# M-LVDS_PHY.net
KiCad netlist of a schematic drawn in Altium Designer
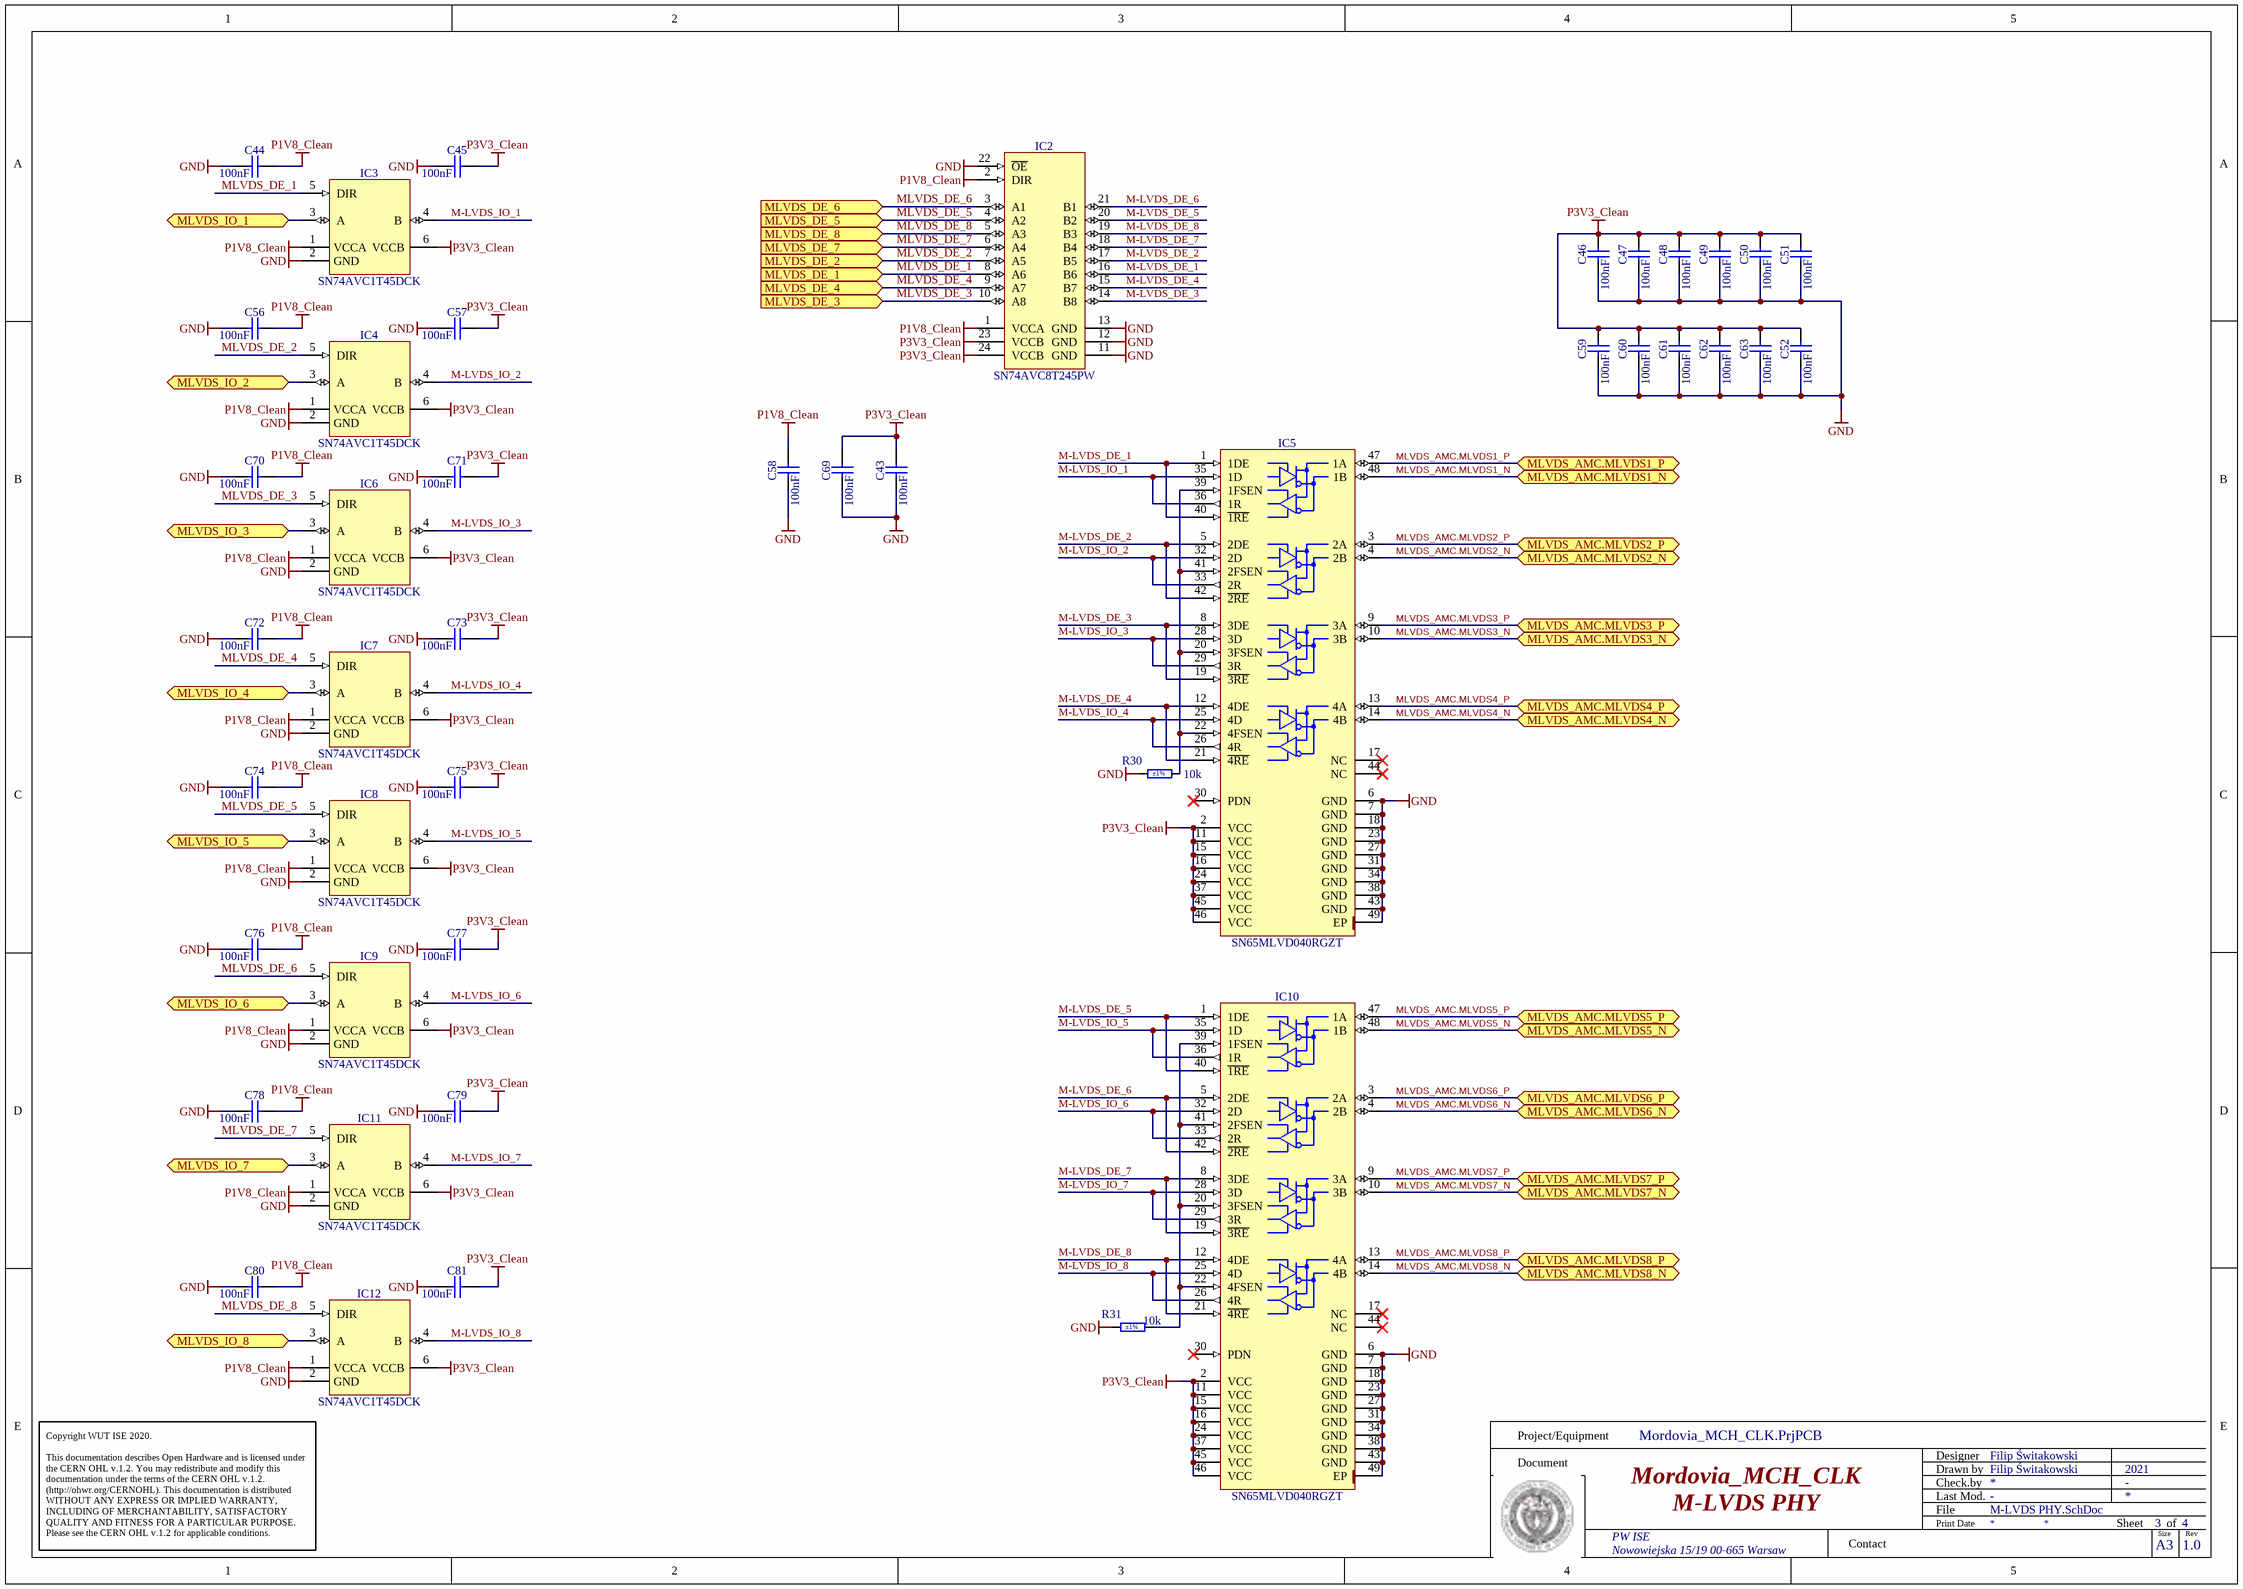
[diagram p0: M-LVDS PHY.SchDoc]

(export (version "E")
  (design (tool "Eeschema 10.0.6"))
  (components
    (comp (ref "C43")
      (value "100nF")
      (footprint "CAPC1005X55N")
      (description "Non-polarised capacitor")
      (fields
        (field (name "PART NUMBER") "CC0402_100NF_50V_10%_X7R")
        (field (name "VOLTAGE") "50V")
        (field (name "AUTHOR") "CERN DEM MR")
      )
      (libsource (lib "Capacitors") (part "Capacitor - non polarized"))
    )
    (comp (ref "C44")
      (value "100nF")
      (footprint "CAPC1005X55N")
      (description "Non-polarised capacitor")
      (fields
        (field (name "PART NUMBER") "CC0402_100NF_50V_10%_X7R")
        (field (name "VOLTAGE") "50V")
        (field (name "AUTHOR") "CERN DEM MR")
      )
      (libsource (lib "Capacitors") (part "Capacitor - non polarized"))
    )
    (comp (ref "C45")
      (value "100nF")
      (footprint "CAPC1005X55N")
      (description "Non-polarised capacitor")
      (fields
        (field (name "PART NUMBER") "CC0402_100NF_50V_10%_X7R")
        (field (name "VOLTAGE") "50V")
        (field (name "AUTHOR") "CERN DEM MR")
      )
      (libsource (lib "Capacitors") (part "Capacitor - non polarized"))
    )
    (comp (ref "C46")
      (value "100nF")
      (footprint "CAPC1005X55N")
      (description "Non-polarised capacitor")
      (fields
        (field (name "PART NUMBER") "CC0402_100NF_50V_10%_X7R")
        (field (name "VOLTAGE") "50V")
        (field (name "AUTHOR") "CERN DEM MR")
      )
      (libsource (lib "Capacitors") (part "Capacitor - non polarized"))
    )
    (comp (ref "C47")
      (value "100nF")
      (footprint "CAPC1005X55N")
      (description "Non-polarised capacitor")
      (fields
        (field (name "PART NUMBER") "CC0402_100NF_50V_10%_X7R")
        (field (name "VOLTAGE") "50V")
        (field (name "AUTHOR") "CERN DEM MR")
      )
      (libsource (lib "Capacitors") (part "Capacitor - non polarized"))
    )
    (comp (ref "C48")
      (value "100nF")
      (footprint "CAPC1005X55N")
      (description "Non-polarised capacitor")
      (fields
        (field (name "PART NUMBER") "CC0402_100NF_50V_10%_X7R")
        (field (name "VOLTAGE") "50V")
        (field (name "AUTHOR") "CERN DEM MR")
      )
      (libsource (lib "Capacitors") (part "Capacitor - non polarized"))
    )
    (comp (ref "C49")
      (value "100nF")
      (footprint "CAPC1005X55N")
      (description "Non-polarised capacitor")
      (fields
        (field (name "PART NUMBER") "CC0402_100NF_50V_10%_X7R")
        (field (name "VOLTAGE") "50V")
        (field (name "AUTHOR") "CERN DEM MR")
      )
      (libsource (lib "Capacitors") (part "Capacitor - non polarized"))
    )
    (comp (ref "C50")
      (value "100nF")
      (footprint "CAPC1005X55N")
      (description "Non-polarised capacitor")
      (fields
        (field (name "PART NUMBER") "CC0402_100NF_50V_10%_X7R")
        (field (name "VOLTAGE") "50V")
        (field (name "AUTHOR") "CERN DEM MR")
      )
      (libsource (lib "Capacitors") (part "Capacitor - non polarized"))
    )
    (comp (ref "C51")
      (value "100nF")
      (footprint "CAPC1005X55N")
      (description "Non-polarised capacitor")
      (fields
        (field (name "PART NUMBER") "CC0402_100NF_50V_10%_X7R")
        (field (name "VOLTAGE") "50V")
        (field (name "AUTHOR") "CERN DEM MR")
      )
      (libsource (lib "Capacitors") (part "Capacitor - non polarized"))
    )
    (comp (ref "C52")
      (value "100nF")
      (footprint "CAPC1005X55N")
      (description "Non-polarised capacitor")
      (fields
        (field (name "PART NUMBER") "CC0402_100NF_50V_10%_X7R")
        (field (name "VOLTAGE") "50V")
        (field (name "AUTHOR") "CERN DEM MR")
      )
      (libsource (lib "Capacitors") (part "Capacitor - non polarized"))
    )
    (comp (ref "C56")
      (value "100nF")
      (footprint "CAPC1005X55N")
      (description "Non-polarised capacitor")
      (fields
        (field (name "PART NUMBER") "CC0402_100NF_50V_10%_X7R")
        (field (name "VOLTAGE") "50V")
        (field (name "AUTHOR") "CERN DEM MR")
      )
      (libsource (lib "Capacitors") (part "Capacitor - non polarized"))
    )
    (comp (ref "C57")
      (value "100nF")
      (footprint "CAPC1005X55N")
      (description "Non-polarised capacitor")
      (fields
        (field (name "PART NUMBER") "CC0402_100NF_50V_10%_X7R")
        (field (name "VOLTAGE") "50V")
        (field (name "AUTHOR") "CERN DEM MR")
      )
      (libsource (lib "Capacitors") (part "Capacitor - non polarized"))
    )
    (comp (ref "C58")
      (value "100nF")
      (footprint "CAPC1005X55N")
      (description "Non-polarised capacitor")
      (fields
        (field (name "PART NUMBER") "CC0402_100NF_50V_10%_X7R")
        (field (name "VOLTAGE") "50V")
        (field (name "AUTHOR") "CERN DEM MR")
      )
      (libsource (lib "Capacitors") (part "Capacitor - non polarized"))
    )
    (comp (ref "C59")
      (value "100nF")
      (footprint "CAPC1005X55N")
      (description "Non-polarised capacitor")
      (fields
        (field (name "PART NUMBER") "CC0402_100NF_50V_10%_X7R")
        (field (name "VOLTAGE") "50V")
        (field (name "AUTHOR") "CERN DEM MR")
      )
      (libsource (lib "Capacitors") (part "Capacitor - non polarized"))
    )
    (comp (ref "C60")
      (value "100nF")
      (footprint "CAPC1005X55N")
      (description "Non-polarised capacitor")
      (fields
        (field (name "PART NUMBER") "CC0402_100NF_50V_10%_X7R")
        (field (name "VOLTAGE") "50V")
        (field (name "AUTHOR") "CERN DEM MR")
      )
      (libsource (lib "Capacitors") (part "Capacitor - non polarized"))
    )
    (comp (ref "C61")
      (value "100nF")
      (footprint "CAPC1005X55N")
      (description "Non-polarised capacitor")
      (fields
        (field (name "PART NUMBER") "CC0402_100NF_50V_10%_X7R")
        (field (name "VOLTAGE") "50V")
        (field (name "AUTHOR") "CERN DEM MR")
      )
      (libsource (lib "Capacitors") (part "Capacitor - non polarized"))
    )
    (comp (ref "C62")
      (value "100nF")
      (footprint "CAPC1005X55N")
      (description "Non-polarised capacitor")
      (fields
        (field (name "PART NUMBER") "CC0402_100NF_50V_10%_X7R")
        (field (name "VOLTAGE") "50V")
        (field (name "AUTHOR") "CERN DEM MR")
      )
      (libsource (lib "Capacitors") (part "Capacitor - non polarized"))
    )
    (comp (ref "C63")
      (value "100nF")
      (footprint "CAPC1005X55N")
      (description "Non-polarised capacitor")
      (fields
        (field (name "PART NUMBER") "CC0402_100NF_50V_10%_X7R")
        (field (name "VOLTAGE") "50V")
        (field (name "AUTHOR") "CERN DEM MR")
      )
      (libsource (lib "Capacitors") (part "Capacitor - non polarized"))
    )
    (comp (ref "C69")
      (value "100nF")
      (footprint "CAPC1005X55N")
      (description "Non-polarised capacitor")
      (fields
        (field (name "PART NUMBER") "CC0402_100NF_50V_10%_X7R")
        (field (name "VOLTAGE") "50V")
        (field (name "AUTHOR") "CERN DEM MR")
      )
      (libsource (lib "Capacitors") (part "Capacitor - non polarized"))
    )
    (comp (ref "C70")
      (value "100nF")
      (footprint "CAPC1005X55N")
      (description "Non-polarised capacitor")
      (fields
        (field (name "PART NUMBER") "CC0402_100NF_50V_10%_X7R")
        (field (name "VOLTAGE") "50V")
        (field (name "AUTHOR") "CERN DEM MR")
      )
      (libsource (lib "Capacitors") (part "Capacitor - non polarized"))
    )
    (comp (ref "C71")
      (value "100nF")
      (footprint "CAPC1005X55N")
      (description "Non-polarised capacitor")
      (fields
        (field (name "PART NUMBER") "CC0402_100NF_50V_10%_X7R")
        (field (name "VOLTAGE") "50V")
        (field (name "AUTHOR") "CERN DEM MR")
      )
      (libsource (lib "Capacitors") (part "Capacitor - non polarized"))
    )
    (comp (ref "C72")
      (value "100nF")
      (footprint "CAPC1005X55N")
      (description "Non-polarised capacitor")
      (fields
        (field (name "PART NUMBER") "CC0402_100NF_50V_10%_X7R")
        (field (name "VOLTAGE") "50V")
        (field (name "AUTHOR") "CERN DEM MR")
      )
      (libsource (lib "Capacitors") (part "Capacitor - non polarized"))
    )
    (comp (ref "C73")
      (value "100nF")
      (footprint "CAPC1005X55N")
      (description "Non-polarised capacitor")
      (fields
        (field (name "PART NUMBER") "CC0402_100NF_50V_10%_X7R")
        (field (name "VOLTAGE") "50V")
        (field (name "AUTHOR") "CERN DEM MR")
      )
      (libsource (lib "Capacitors") (part "Capacitor - non polarized"))
    )
    (comp (ref "C74")
      (value "100nF")
      (footprint "CAPC1005X55N")
      (description "Non-polarised capacitor")
      (fields
        (field (name "PART NUMBER") "CC0402_100NF_50V_10%_X7R")
        (field (name "VOLTAGE") "50V")
        (field (name "AUTHOR") "CERN DEM MR")
      )
      (libsource (lib "Capacitors") (part "Capacitor - non polarized"))
    )
    (comp (ref "C75")
      (value "100nF")
      (footprint "CAPC1005X55N")
      (description "Non-polarised capacitor")
      (fields
        (field (name "PART NUMBER") "CC0402_100NF_50V_10%_X7R")
        (field (name "VOLTAGE") "50V")
        (field (name "AUTHOR") "CERN DEM MR")
      )
      (libsource (lib "Capacitors") (part "Capacitor - non polarized"))
    )
    (comp (ref "C76")
      (value "100nF")
      (footprint "CAPC1005X55N")
      (description "Non-polarised capacitor")
      (fields
        (field (name "PART NUMBER") "CC0402_100NF_50V_10%_X7R")
        (field (name "VOLTAGE") "50V")
        (field (name "AUTHOR") "CERN DEM MR")
      )
      (libsource (lib "Capacitors") (part "Capacitor - non polarized"))
    )
    (comp (ref "C77")
      (value "100nF")
      (footprint "CAPC1005X55N")
      (description "Non-polarised capacitor")
      (fields
        (field (name "PART NUMBER") "CC0402_100NF_50V_10%_X7R")
        (field (name "VOLTAGE") "50V")
        (field (name "AUTHOR") "CERN DEM MR")
      )
      (libsource (lib "Capacitors") (part "Capacitor - non polarized"))
    )
    (comp (ref "C78")
      (value "100nF")
      (footprint "CAPC1005X55N")
      (description "Non-polarised capacitor")
      (fields
        (field (name "PART NUMBER") "CC0402_100NF_50V_10%_X7R")
        (field (name "VOLTAGE") "50V")
        (field (name "AUTHOR") "CERN DEM MR")
      )
      (libsource (lib "Capacitors") (part "Capacitor - non polarized"))
    )
    (comp (ref "C79")
      (value "100nF")
      (footprint "CAPC1005X55N")
      (description "Non-polarised capacitor")
      (fields
        (field (name "PART NUMBER") "CC0402_100NF_50V_10%_X7R")
        (field (name "VOLTAGE") "50V")
        (field (name "AUTHOR") "CERN DEM MR")
      )
      (libsource (lib "Capacitors") (part "Capacitor - non polarized"))
    )
    (comp (ref "C80")
      (value "100nF")
      (footprint "CAPC1005X55N")
      (description "Non-polarised capacitor")
      (fields
        (field (name "PART NUMBER") "CC0402_100NF_50V_10%_X7R")
        (field (name "VOLTAGE") "50V")
        (field (name "AUTHOR") "CERN DEM MR")
      )
      (libsource (lib "Capacitors") (part "Capacitor - non polarized"))
    )
    (comp (ref "C81")
      (value "100nF")
      (footprint "CAPC1005X55N")
      (description "Non-polarised capacitor")
      (fields
        (field (name "PART NUMBER") "CC0402_100NF_50V_10%_X7R")
        (field (name "VOLTAGE") "50V")
        (field (name "AUTHOR") "CERN DEM MR")
      )
      (libsource (lib "Capacitors") (part "Capacitor - non polarized"))
    )
    (comp (ref "IC2")
      (value "SN74AVC8T245PW")
      (footprint "SOP65P640X120-24N")
      (description "8-Bit Dual-Supply Bus Transceiver With Configurable Voltage Translation and 3-State Outputs")
      (fields (field (name "MANUFACTURER") "TEXAS INSTRUMENTS") (field (name "AUTHOR") "CERN DEM JLC"))
      (libsource (lib "ICs And Semiconductors") (part "748T245"))
    )
    (comp (ref "IC3")
      (value "SN74AVC1T45DCK")
      (footprint "SOT65P210X110-6N")
      (description "Single-Bit Dual-Supply Bus Transceiver")
      (fields
        (field (name "PART NUMBER") "SN74AVC1T45DCKR")
        (field (name "MANUFACTURER") "TEXAS INSTRUMENTS")
        (field (name "AUTHOR") "CERN DEM JLC")
      )
      (libsource (lib "ICs And Semiconductors") (part "741T45"))
    )
    (comp (ref "IC4")
      (value "SN74AVC1T45DCK")
      (footprint "SOT65P210X110-6N")
      (description "Single-Bit Dual-Supply Bus Transceiver")
      (fields
        (field (name "PART NUMBER") "SN74AVC1T45DCKR")
        (field (name "MANUFACTURER") "TEXAS INSTRUMENTS")
        (field (name "AUTHOR") "CERN DEM JLC")
      )
      (libsource (lib "ICs And Semiconductors") (part "741T45"))
    )
    (comp (ref "IC5")
      (value "SN65MLVD040RGZT")
      (footprint "QFN50P700X700X100-49N-S420")
      (description "4-Channel Half-Duplex M-LVDS Line Transceiver")
      (fields (field (name "MANUFACTURER") "TEXAS INSTRUMENTS") (field (name "AUTHOR") "CERN DEM JLC"))
      (libsource (lib "ICs And Semiconductors") (part "SN65MLVD040"))
    )
    (comp (ref "IC6")
      (value "SN74AVC1T45DCK")
      (footprint "SOT65P210X110-6N")
      (description "Single-Bit Dual-Supply Bus Transceiver")
      (fields
        (field (name "PART NUMBER") "SN74AVC1T45DCKR")
        (field (name "MANUFACTURER") "TEXAS INSTRUMENTS")
        (field (name "AUTHOR") "CERN DEM JLC")
      )
      (libsource (lib "ICs And Semiconductors") (part "741T45"))
    )
    (comp (ref "IC7")
      (value "SN74AVC1T45DCK")
      (footprint "SOT65P210X110-6N")
      (description "Single-Bit Dual-Supply Bus Transceiver")
      (fields
        (field (name "PART NUMBER") "SN74AVC1T45DCKR")
        (field (name "MANUFACTURER") "TEXAS INSTRUMENTS")
        (field (name "AUTHOR") "CERN DEM JLC")
      )
      (libsource (lib "ICs And Semiconductors") (part "741T45"))
    )
    (comp (ref "IC8")
      (value "SN74AVC1T45DCK")
      (footprint "SOT65P210X110-6N")
      (description "Single-Bit Dual-Supply Bus Transceiver")
      (fields
        (field (name "PART NUMBER") "SN74AVC1T45DCKR")
        (field (name "MANUFACTURER") "TEXAS INSTRUMENTS")
        (field (name "AUTHOR") "CERN DEM JLC")
      )
      (libsource (lib "ICs And Semiconductors") (part "741T45"))
    )
    (comp (ref "IC9")
      (value "SN74AVC1T45DCK")
      (footprint "SOT65P210X110-6N")
      (description "Single-Bit Dual-Supply Bus Transceiver")
      (fields
        (field (name "PART NUMBER") "SN74AVC1T45DCKR")
        (field (name "MANUFACTURER") "TEXAS INSTRUMENTS")
        (field (name "AUTHOR") "CERN DEM JLC")
      )
      (libsource (lib "ICs And Semiconductors") (part "741T45"))
    )
    (comp (ref "IC10")
      (value "SN65MLVD040RGZT")
      (footprint "QFN50P700X700X100-49N-S420")
      (description "4-Channel Half-Duplex M-LVDS Line Transceiver")
      (fields (field (name "MANUFACTURER") "TEXAS INSTRUMENTS") (field (name "AUTHOR") "CERN DEM JLC"))
      (libsource (lib "ICs And Semiconductors") (part "SN65MLVD040"))
    )
    (comp (ref "IC11")
      (value "SN74AVC1T45DCK")
      (footprint "SOT65P210X110-6N")
      (description "Single-Bit Dual-Supply Bus Transceiver")
      (fields
        (field (name "PART NUMBER") "SN74AVC1T45DCKR")
        (field (name "MANUFACTURER") "TEXAS INSTRUMENTS")
        (field (name "AUTHOR") "CERN DEM JLC")
      )
      (libsource (lib "ICs And Semiconductors") (part "741T45"))
    )
    (comp (ref "IC12")
      (value "SN74AVC1T45DCK")
      (footprint "SOT65P210X110-6N")
      (description "Single-Bit Dual-Supply Bus Transceiver")
      (fields
        (field (name "PART NUMBER") "SN74AVC1T45DCKR")
        (field (name "MANUFACTURER") "TEXAS INSTRUMENTS")
        (field (name "AUTHOR") "CERN DEM JLC")
      )
      (libsource (lib "ICs And Semiconductors") (part "741T45"))
    )
    (comp (ref "R30")
      (value "10k")
      (footprint "RESC1005X40N")
      (description "Resistor - 1%")
      (fields
        (field (name "TOLERANCE") "±1%")
        (field (name "PART NUMBER") "R0402_10K_1%_0.0625W_100PPM")
        (field (name "POWER") "0.0625W")
        (field (name "AUTHOR") "CERN DEM JLC")
      )
      (libsource (lib "Resistors") (part "Resistor - 1%"))
    )
    (comp (ref "R31")
      (value "10k")
      (footprint "RESC1005X40N")
      (description "Resistor - 1%")
      (fields
        (field (name "TOLERANCE") "±1%")
        (field (name "PART NUMBER") "R0402_10K_1%_0.0625W_100PPM")
        (field (name "POWER") "0.0625W")
        (field (name "AUTHOR") "CERN DEM JLC")
      )
      (libsource (lib "Resistors") (part "Resistor - 1%"))
    )
  )
  (nets
    (net (code "1") (name "/M-LVDS_DE_1") (class "Default")
      (node (ref "IC2") (pin "16") (pinfunction "B6_16") (pintype "bidirectional"))
      (node (ref "IC5") (pin "1") (pinfunction "1DE_1") (pintype "input"))
      (node (ref "IC5") (pin "40") (pinfunction "~{1RE}_40") (pintype "input"))
    )
    (net (code "2") (name "/M-LVDS_DE_2") (class "Default")
      (node (ref "IC2") (pin "17") (pinfunction "B5_17") (pintype "bidirectional"))
      (node (ref "IC5") (pin "42") (pinfunction "~{2RE}_42") (pintype "input"))
      (node (ref "IC5") (pin "5") (pinfunction "2DE_5") (pintype "input"))
    )
    (net (code "3") (name "/M-LVDS_DE_3") (class "Default")
      (node (ref "IC2") (pin "14") (pinfunction "B8_14") (pintype "bidirectional"))
      (node (ref "IC5") (pin "19") (pinfunction "~{3RE}_19") (pintype "input"))
      (node (ref "IC5") (pin "8") (pinfunction "3DE_8") (pintype "input"))
    )
    (net (code "4") (name "/M-LVDS_DE_4") (class "Default")
      (node (ref "IC2") (pin "15") (pinfunction "B7_15") (pintype "bidirectional"))
      (node (ref "IC5") (pin "12") (pinfunction "4DE_12") (pintype "input"))
      (node (ref "IC5") (pin "21") (pinfunction "~{4RE}_21") (pintype "input"))
    )
    (net (code "5") (name "/M-LVDS_DE_5") (class "Default")
      (node (ref "IC10") (pin "1") (pinfunction "1DE_1") (pintype "input"))
      (node (ref "IC10") (pin "40") (pinfunction "~{1RE}_40") (pintype "input"))
      (node (ref "IC2") (pin "20") (pinfunction "B2_20") (pintype "bidirectional"))
    )
    (net (code "6") (name "/M-LVDS_DE_6") (class "Default")
      (node (ref "IC10") (pin "42") (pinfunction "~{2RE}_42") (pintype "input"))
      (node (ref "IC10") (pin "5") (pinfunction "2DE_5") (pintype "input"))
      (node (ref "IC2") (pin "21") (pinfunction "B1_21") (pintype "bidirectional"))
    )
    (net (code "7") (name "/M-LVDS_DE_7") (class "Default")
      (node (ref "IC10") (pin "19") (pinfunction "~{3RE}_19") (pintype "input"))
      (node (ref "IC10") (pin "8") (pinfunction "3DE_8") (pintype "input"))
      (node (ref "IC2") (pin "18") (pinfunction "B4_18") (pintype "bidirectional"))
    )
    (net (code "8") (name "/M-LVDS_DE_8") (class "Default")
      (node (ref "IC10") (pin "12") (pinfunction "4DE_12") (pintype "input"))
      (node (ref "IC10") (pin "21") (pinfunction "~{4RE}_21") (pintype "input"))
      (node (ref "IC2") (pin "19") (pinfunction "B3_19") (pintype "bidirectional"))
    )
    (net (code "9") (name "/M-LVDS_IO_1") (class "Default")
      (node (ref "IC3") (pin "4") (pinfunction "B_4") (pintype "bidirectional"))
      (node (ref "IC5") (pin "35") (pinfunction "1D_35") (pintype "input"))
      (node (ref "IC5") (pin "36") (pinfunction "1R_36") (pintype "output"))
    )
    (net (code "10") (name "/M-LVDS_IO_2") (class "Default")
      (node (ref "IC4") (pin "4") (pinfunction "B_4") (pintype "bidirectional"))
      (node (ref "IC5") (pin "32") (pinfunction "2D_32") (pintype "input"))
      (node (ref "IC5") (pin "33") (pinfunction "2R_33") (pintype "output"))
    )
    (net (code "11") (name "/M-LVDS_IO_3") (class "Default")
      (node (ref "IC5") (pin "28") (pinfunction "3D_28") (pintype "input"))
      (node (ref "IC5") (pin "29") (pinfunction "3R_29") (pintype "output"))
      (node (ref "IC6") (pin "4") (pinfunction "B_4") (pintype "bidirectional"))
    )
    (net (code "12") (name "/M-LVDS_IO_4") (class "Default")
      (node (ref "IC5") (pin "25") (pinfunction "4D_25") (pintype "input"))
      (node (ref "IC5") (pin "26") (pinfunction "4R_26") (pintype "output"))
      (node (ref "IC7") (pin "4") (pinfunction "B_4") (pintype "bidirectional"))
    )
    (net (code "13") (name "/M-LVDS_IO_5") (class "Default")
      (node (ref "IC10") (pin "35") (pinfunction "1D_35") (pintype "input"))
      (node (ref "IC10") (pin "36") (pinfunction "1R_36") (pintype "output"))
      (node (ref "IC8") (pin "4") (pinfunction "B_4") (pintype "bidirectional"))
    )
    (net (code "14") (name "/M-LVDS_IO_6") (class "Default")
      (node (ref "IC10") (pin "32") (pinfunction "2D_32") (pintype "input"))
      (node (ref "IC10") (pin "33") (pinfunction "2R_33") (pintype "output"))
      (node (ref "IC9") (pin "4") (pinfunction "B_4") (pintype "bidirectional"))
    )
    (net (code "15") (name "/M-LVDS_IO_7") (class "Default")
      (node (ref "IC10") (pin "28") (pinfunction "3D_28") (pintype "input"))
      (node (ref "IC10") (pin "29") (pinfunction "3R_29") (pintype "output"))
      (node (ref "IC11") (pin "4") (pinfunction "B_4") (pintype "bidirectional"))
    )
    (net (code "16") (name "/M-LVDS_IO_8") (class "Default")
      (node (ref "IC10") (pin "25") (pinfunction "4D_25") (pintype "input"))
      (node (ref "IC10") (pin "26") (pinfunction "4R_26") (pintype "output"))
      (node (ref "IC12") (pin "4") (pinfunction "B_4") (pintype "bidirectional"))
    )
    (net (code "17") (name "/MLVDS_AMC.MLVDS1_N") (class "Default")
      (node (ref "IC5") (pin "48") (pinfunction "1B_48") (pintype "bidirectional"))
    )
    (net (code "18") (name "/MLVDS_AMC.MLVDS1_P") (class "Default")
      (node (ref "IC5") (pin "47") (pinfunction "1A_47") (pintype "bidirectional"))
    )
    (net (code "19") (name "/MLVDS_AMC.MLVDS2_N") (class "Default")
      (node (ref "IC5") (pin "4") (pinfunction "2B_4") (pintype "bidirectional"))
    )
    (net (code "20") (name "/MLVDS_AMC.MLVDS2_P") (class "Default")
      (node (ref "IC5") (pin "3") (pinfunction "2A_3") (pintype "bidirectional"))
    )
    (net (code "21") (name "/MLVDS_AMC.MLVDS3_N") (class "Default")
      (node (ref "IC5") (pin "10") (pinfunction "3B_10") (pintype "bidirectional"))
    )
    (net (code "22") (name "/MLVDS_AMC.MLVDS3_P") (class "Default")
      (node (ref "IC5") (pin "9") (pinfunction "3A_9") (pintype "bidirectional"))
    )
    (net (code "23") (name "/MLVDS_AMC.MLVDS4_N") (class "Default")
      (node (ref "IC5") (pin "14") (pinfunction "4B_14") (pintype "bidirectional"))
    )
    (net (code "24") (name "/MLVDS_AMC.MLVDS4_P") (class "Default")
      (node (ref "IC5") (pin "13") (pinfunction "4A_13") (pintype "bidirectional"))
    )
    (net (code "25") (name "/MLVDS_AMC.MLVDS5_N") (class "Default")
      (node (ref "IC10") (pin "48") (pinfunction "1B_48") (pintype "bidirectional"))
    )
    (net (code "26") (name "/MLVDS_AMC.MLVDS5_P") (class "Default")
      (node (ref "IC10") (pin "47") (pinfunction "1A_47") (pintype "bidirectional"))
    )
    (net (code "27") (name "/MLVDS_AMC.MLVDS6_N") (class "Default")
      (node (ref "IC10") (pin "4") (pinfunction "2B_4") (pintype "bidirectional"))
    )
    (net (code "28") (name "/MLVDS_AMC.MLVDS6_P") (class "Default")
      (node (ref "IC10") (pin "3") (pinfunction "2A_3") (pintype "bidirectional"))
    )
    (net (code "29") (name "/MLVDS_AMC.MLVDS7_N") (class "Default")
      (node (ref "IC10") (pin "10") (pinfunction "3B_10") (pintype "bidirectional"))
    )
    (net (code "30") (name "/MLVDS_AMC.MLVDS7_P") (class "Default")
      (node (ref "IC10") (pin "9") (pinfunction "3A_9") (pintype "bidirectional"))
    )
    (net (code "31") (name "/MLVDS_AMC.MLVDS8_N") (class "Default")
      (node (ref "IC10") (pin "14") (pinfunction "4B_14") (pintype "bidirectional"))
    )
    (net (code "32") (name "/MLVDS_AMC.MLVDS8_P") (class "Default")
      (node (ref "IC10") (pin "13") (pinfunction "4A_13") (pintype "bidirectional"))
    )
    (net (code "33") (name "/MLVDS_DE_1") (class "Default")
      (node (ref "IC2") (pin "8") (pinfunction "A6_8") (pintype "bidirectional"))
      (node (ref "IC3") (pin "5") (pinfunction "DIR_5") (pintype "input"))
    )
    (net (code "34") (name "/MLVDS_DE_2") (class "Default")
      (node (ref "IC2") (pin "7") (pinfunction "A5_7") (pintype "bidirectional"))
      (node (ref "IC4") (pin "5") (pinfunction "DIR_5") (pintype "input"))
    )
    (net (code "35") (name "/MLVDS_DE_3") (class "Default")
      (node (ref "IC2") (pin "10") (pinfunction "A8_10") (pintype "bidirectional"))
      (node (ref "IC6") (pin "5") (pinfunction "DIR_5") (pintype "input"))
    )
    (net (code "36") (name "/MLVDS_DE_4") (class "Default")
      (node (ref "IC2") (pin "9") (pinfunction "A7_9") (pintype "bidirectional"))
      (node (ref "IC7") (pin "5") (pinfunction "DIR_5") (pintype "input"))
    )
    (net (code "37") (name "/MLVDS_DE_5") (class "Default")
      (node (ref "IC2") (pin "4") (pinfunction "A2_4") (pintype "bidirectional"))
      (node (ref "IC8") (pin "5") (pinfunction "DIR_5") (pintype "input"))
    )
    (net (code "38") (name "/MLVDS_DE_6") (class "Default")
      (node (ref "IC2") (pin "3") (pinfunction "A1_3") (pintype "bidirectional"))
      (node (ref "IC9") (pin "5") (pinfunction "DIR_5") (pintype "input"))
    )
    (net (code "39") (name "/MLVDS_DE_7") (class "Default")
      (node (ref "IC11") (pin "5") (pinfunction "DIR_5") (pintype "input"))
      (node (ref "IC2") (pin "6") (pinfunction "A4_6") (pintype "bidirectional"))
    )
    (net (code "40") (name "/MLVDS_DE_8") (class "Default")
      (node (ref "IC12") (pin "5") (pinfunction "DIR_5") (pintype "input"))
      (node (ref "IC2") (pin "5") (pinfunction "A3_5") (pintype "bidirectional"))
    )
    (net (code "41") (name "/MLVDS_IO_1") (class "Default")
      (node (ref "IC3") (pin "3") (pinfunction "A_3") (pintype "bidirectional"))
    )
    (net (code "42") (name "/MLVDS_IO_2") (class "Default")
      (node (ref "IC4") (pin "3") (pinfunction "A_3") (pintype "bidirectional"))
    )
    (net (code "43") (name "/MLVDS_IO_3") (class "Default")
      (node (ref "IC6") (pin "3") (pinfunction "A_3") (pintype "bidirectional"))
    )
    (net (code "44") (name "/MLVDS_IO_4") (class "Default")
      (node (ref "IC7") (pin "3") (pinfunction "A_3") (pintype "bidirectional"))
    )
    (net (code "45") (name "/MLVDS_IO_5") (class "Default")
      (node (ref "IC8") (pin "3") (pinfunction "A_3") (pintype "bidirectional"))
    )
    (net (code "46") (name "/MLVDS_IO_6") (class "Default")
      (node (ref "IC9") (pin "3") (pinfunction "A_3") (pintype "bidirectional"))
    )
    (net (code "47") (name "/MLVDS_IO_7") (class "Default")
      (node (ref "IC11") (pin "3") (pinfunction "A_3") (pintype "bidirectional"))
    )
    (net (code "48") (name "/MLVDS_IO_8") (class "Default")
      (node (ref "IC12") (pin "3") (pinfunction "A_3") (pintype "bidirectional"))
    )
    (net (code "49") (name "GND") (class "Default")
      (node (ref "C43") (pin "1") (pinfunction "1_1") (pintype "passive"))
      (node (ref "C44") (pin "1") (pinfunction "1_1") (pintype "passive"))
      (node (ref "C45") (pin "1") (pinfunction "1_1") (pintype "passive"))
      (node (ref "C46") (pin "1") (pinfunction "1_1") (pintype "passive"))
      (node (ref "C47") (pin "1") (pinfunction "1_1") (pintype "passive"))
      (node (ref "C48") (pin "1") (pinfunction "1_1") (pintype "passive"))
      (node (ref "C49") (pin "1") (pinfunction "1_1") (pintype "passive"))
      (node (ref "C50") (pin "1") (pinfunction "1_1") (pintype "passive"))
      (node (ref "C51") (pin "1") (pinfunction "1_1") (pintype "passive"))
      (node (ref "C52") (pin "1") (pinfunction "1_1") (pintype "passive"))
      (node (ref "C56") (pin "1") (pinfunction "1_1") (pintype "passive"))
      (node (ref "C57") (pin "1") (pinfunction "1_1") (pintype "passive"))
      (node (ref "C58") (pin "1") (pinfunction "1_1") (pintype "passive"))
      (node (ref "C59") (pin "1") (pinfunction "1_1") (pintype "passive"))
      (node (ref "C60") (pin "1") (pinfunction "1_1") (pintype "passive"))
      (node (ref "C61") (pin "1") (pinfunction "1_1") (pintype "passive"))
      (node (ref "C62") (pin "1") (pinfunction "1_1") (pintype "passive"))
      (node (ref "C63") (pin "1") (pinfunction "1_1") (pintype "passive"))
      (node (ref "C69") (pin "1") (pinfunction "1_1") (pintype "passive"))
      (node (ref "C70") (pin "1") (pinfunction "1_1") (pintype "passive"))
      (node (ref "C71") (pin "1") (pinfunction "1_1") (pintype "passive"))
      (node (ref "C72") (pin "1") (pinfunction "1_1") (pintype "passive"))
      (node (ref "C73") (pin "1") (pinfunction "1_1") (pintype "passive"))
      (node (ref "C74") (pin "1") (pinfunction "1_1") (pintype "passive"))
      (node (ref "C75") (pin "1") (pinfunction "1_1") (pintype "passive"))
      (node (ref "C76") (pin "1") (pinfunction "1_1") (pintype "passive"))
      (node (ref "C77") (pin "1") (pinfunction "1_1") (pintype "passive"))
      (node (ref "C78") (pin "1") (pinfunction "1_1") (pintype "passive"))
      (node (ref "C79") (pin "1") (pinfunction "1_1") (pintype "passive"))
      (node (ref "C80") (pin "1") (pinfunction "1_1") (pintype "passive"))
      (node (ref "C81") (pin "1") (pinfunction "1_1") (pintype "passive"))
      (node (ref "IC10") (pin "18") (pinfunction "GND_18") (pintype "power_in"))
      (node (ref "IC10") (pin "23") (pinfunction "GND_23") (pintype "power_in"))
      (node (ref "IC10") (pin "27") (pinfunction "GND_27") (pintype "power_in"))
      (node (ref "IC10") (pin "31") (pinfunction "GND_31") (pintype "power_in"))
      (node (ref "IC10") (pin "34") (pinfunction "GND_34") (pintype "power_in"))
      (node (ref "IC10") (pin "38") (pinfunction "GND_38") (pintype "power_in"))
      (node (ref "IC10") (pin "43") (pinfunction "GND_43") (pintype "power_in"))
      (node (ref "IC10") (pin "49") (pinfunction "EP_49") (pintype "power_in"))
      (node (ref "IC10") (pin "6") (pinfunction "GND_6") (pintype "power_in"))
      (node (ref "IC10") (pin "7") (pinfunction "GND_7") (pintype "power_in"))
      (node (ref "IC11") (pin "2") (pinfunction "GND_2") (pintype "power_in"))
      (node (ref "IC12") (pin "2") (pinfunction "GND_2") (pintype "power_in"))
      (node (ref "IC2") (pin "11") (pinfunction "GND_11") (pintype "power_in"))
      (node (ref "IC2") (pin "12") (pinfunction "GND_12") (pintype "power_in"))
      (node (ref "IC2") (pin "13") (pinfunction "GND_13") (pintype "power_in"))
      (node (ref "IC2") (pin "22") (pinfunction "~{OE}_22") (pintype "input"))
      (node (ref "IC3") (pin "2") (pinfunction "GND_2") (pintype "power_in"))
      (node (ref "IC4") (pin "2") (pinfunction "GND_2") (pintype "power_in"))
      (node (ref "IC5") (pin "18") (pinfunction "GND_18") (pintype "power_in"))
      (node (ref "IC5") (pin "23") (pinfunction "GND_23") (pintype "power_in"))
      (node (ref "IC5") (pin "27") (pinfunction "GND_27") (pintype "power_in"))
      (node (ref "IC5") (pin "31") (pinfunction "GND_31") (pintype "power_in"))
      (node (ref "IC5") (pin "34") (pinfunction "GND_34") (pintype "power_in"))
      (node (ref "IC5") (pin "38") (pinfunction "GND_38") (pintype "power_in"))
      (node (ref "IC5") (pin "43") (pinfunction "GND_43") (pintype "power_in"))
      (node (ref "IC5") (pin "49") (pinfunction "EP_49") (pintype "power_in"))
      (node (ref "IC5") (pin "6") (pinfunction "GND_6") (pintype "power_in"))
      (node (ref "IC5") (pin "7") (pinfunction "GND_7") (pintype "power_in"))
      (node (ref "IC6") (pin "2") (pinfunction "GND_2") (pintype "power_in"))
      (node (ref "IC7") (pin "2") (pinfunction "GND_2") (pintype "power_in"))
      (node (ref "IC8") (pin "2") (pinfunction "GND_2") (pintype "power_in"))
      (node (ref "IC9") (pin "2") (pinfunction "GND_2") (pintype "power_in"))
      (node (ref "R30") (pin "1") (pinfunction "1_1") (pintype "passive"))
      (node (ref "R31") (pin "1") (pinfunction "1_1") (pintype "passive"))
    )
    (net (code "50") (name "Net-(IC5-1FSEN)") (class "Default")
      (node (ref "IC5") (pin "20") (pinfunction "3FSEN_20") (pintype "input"))
      (node (ref "IC5") (pin "22") (pinfunction "4FSEN_22") (pintype "input"))
      (node (ref "IC5") (pin "39") (pinfunction "1FSEN_39") (pintype "input"))
      (node (ref "IC5") (pin "41") (pinfunction "2FSEN_41") (pintype "input"))
      (node (ref "R30") (pin "2") (pinfunction "2_2") (pintype "passive"))
    )
    (net (code "51") (name "Net-(IC10-1FSEN)") (class "Default")
      (node (ref "IC10") (pin "20") (pinfunction "3FSEN_20") (pintype "input"))
      (node (ref "IC10") (pin "22") (pinfunction "4FSEN_22") (pintype "input"))
      (node (ref "IC10") (pin "39") (pinfunction "1FSEN_39") (pintype "input"))
      (node (ref "IC10") (pin "41") (pinfunction "2FSEN_41") (pintype "input"))
      (node (ref "R31") (pin "2") (pinfunction "2_2") (pintype "passive"))
    )
    (net (code "52") (name "P1V8_Clean") (class "Default")
      (node (ref "C44") (pin "2") (pinfunction "2_2") (pintype "passive"))
      (node (ref "C56") (pin "2") (pinfunction "2_2") (pintype "passive"))
      (node (ref "C58") (pin "2") (pinfunction "2_2") (pintype "passive"))
      (node (ref "C70") (pin "2") (pinfunction "2_2") (pintype "passive"))
      (node (ref "C72") (pin "2") (pinfunction "2_2") (pintype "passive"))
      (node (ref "C74") (pin "2") (pinfunction "2_2") (pintype "passive"))
      (node (ref "C76") (pin "2") (pinfunction "2_2") (pintype "passive"))
      (node (ref "C78") (pin "2") (pinfunction "2_2") (pintype "passive"))
      (node (ref "C80") (pin "2") (pinfunction "2_2") (pintype "passive"))
      (node (ref "IC11") (pin "1") (pinfunction "VCCA_1") (pintype "power_in"))
      (node (ref "IC12") (pin "1") (pinfunction "VCCA_1") (pintype "power_in"))
      (node (ref "IC2") (pin "1") (pinfunction "VCCA_1") (pintype "power_in"))
      (node (ref "IC2") (pin "2") (pinfunction "DIR_2") (pintype "input"))
      (node (ref "IC3") (pin "1") (pinfunction "VCCA_1") (pintype "power_in"))
      (node (ref "IC4") (pin "1") (pinfunction "VCCA_1") (pintype "power_in"))
      (node (ref "IC6") (pin "1") (pinfunction "VCCA_1") (pintype "power_in"))
      (node (ref "IC7") (pin "1") (pinfunction "VCCA_1") (pintype "power_in"))
      (node (ref "IC8") (pin "1") (pinfunction "VCCA_1") (pintype "power_in"))
      (node (ref "IC9") (pin "1") (pinfunction "VCCA_1") (pintype "power_in"))
    )
    (net (code "53") (name "P3V3_Clean") (class "Default")
      (node (ref "C43") (pin "2") (pinfunction "2_2") (pintype "passive"))
      (node (ref "C45") (pin "2") (pinfunction "2_2") (pintype "passive"))
      (node (ref "C46") (pin "2") (pinfunction "2_2") (pintype "passive"))
      (node (ref "C47") (pin "2") (pinfunction "2_2") (pintype "passive"))
      (node (ref "C48") (pin "2") (pinfunction "2_2") (pintype "passive"))
      (node (ref "C49") (pin "2") (pinfunction "2_2") (pintype "passive"))
      (node (ref "C50") (pin "2") (pinfunction "2_2") (pintype "passive"))
      (node (ref "C51") (pin "2") (pinfunction "2_2") (pintype "passive"))
      (node (ref "C52") (pin "2") (pinfunction "2_2") (pintype "passive"))
      (node (ref "C57") (pin "2") (pinfunction "2_2") (pintype "passive"))
      (node (ref "C59") (pin "2") (pinfunction "2_2") (pintype "passive"))
      (node (ref "C60") (pin "2") (pinfunction "2_2") (pintype "passive"))
      (node (ref "C61") (pin "2") (pinfunction "2_2") (pintype "passive"))
      (node (ref "C62") (pin "2") (pinfunction "2_2") (pintype "passive"))
      (node (ref "C63") (pin "2") (pinfunction "2_2") (pintype "passive"))
      (node (ref "C69") (pin "2") (pinfunction "2_2") (pintype "passive"))
      (node (ref "C71") (pin "2") (pinfunction "2_2") (pintype "passive"))
      (node (ref "C73") (pin "2") (pinfunction "2_2") (pintype "passive"))
      (node (ref "C75") (pin "2") (pinfunction "2_2") (pintype "passive"))
      (node (ref "C77") (pin "2") (pinfunction "2_2") (pintype "passive"))
      (node (ref "C79") (pin "2") (pinfunction "2_2") (pintype "passive"))
      (node (ref "C81") (pin "2") (pinfunction "2_2") (pintype "passive"))
      (node (ref "IC10") (pin "11") (pinfunction "VCC_11") (pintype "power_in"))
      (node (ref "IC10") (pin "15") (pinfunction "VCC_15") (pintype "power_in"))
      (node (ref "IC10") (pin "16") (pinfunction "VCC_16") (pintype "power_in"))
      (node (ref "IC10") (pin "2") (pinfunction "VCC_2") (pintype "power_in"))
      (node (ref "IC10") (pin "24") (pinfunction "VCC_24") (pintype "power_in"))
      (node (ref "IC10") (pin "37") (pinfunction "VCC_37") (pintype "power_in"))
      (node (ref "IC10") (pin "45") (pinfunction "VCC_45") (pintype "power_in"))
      (node (ref "IC10") (pin "46") (pinfunction "VCC_46") (pintype "power_in"))
      (node (ref "IC11") (pin "6") (pinfunction "VCCB_6") (pintype "power_in"))
      (node (ref "IC12") (pin "6") (pinfunction "VCCB_6") (pintype "power_in"))
      (node (ref "IC2") (pin "23") (pinfunction "VCCB_23") (pintype "power_in"))
      (node (ref "IC2") (pin "24") (pinfunction "VCCB_24") (pintype "power_in"))
      (node (ref "IC3") (pin "6") (pinfunction "VCCB_6") (pintype "power_in"))
      (node (ref "IC4") (pin "6") (pinfunction "VCCB_6") (pintype "power_in"))
      (node (ref "IC5") (pin "11") (pinfunction "VCC_11") (pintype "power_in"))
      (node (ref "IC5") (pin "15") (pinfunction "VCC_15") (pintype "power_in"))
      (node (ref "IC5") (pin "16") (pinfunction "VCC_16") (pintype "power_in"))
      (node (ref "IC5") (pin "2") (pinfunction "VCC_2") (pintype "power_in"))
      (node (ref "IC5") (pin "24") (pinfunction "VCC_24") (pintype "power_in"))
      (node (ref "IC5") (pin "37") (pinfunction "VCC_37") (pintype "power_in"))
      (node (ref "IC5") (pin "45") (pinfunction "VCC_45") (pintype "power_in"))
      (node (ref "IC5") (pin "46") (pinfunction "VCC_46") (pintype "power_in"))
      (node (ref "IC6") (pin "6") (pinfunction "VCCB_6") (pintype "power_in"))
      (node (ref "IC7") (pin "6") (pinfunction "VCCB_6") (pintype "power_in"))
      (node (ref "IC8") (pin "6") (pinfunction "VCCB_6") (pintype "power_in"))
      (node (ref "IC9") (pin "6") (pinfunction "VCCB_6") (pintype "power_in"))
    )
    (net (code "54") (name "unconnected-(IC5-NC-Pad17)") (class "Default")
      (node (ref "IC5") (pin "17") (pinfunction "NC_17") (pintype "passive+no_connect"))
    )
    (net (code "55") (name "unconnected-(IC5-NC-Pad44)") (class "Default")
      (node (ref "IC5") (pin "44") (pinfunction "NC_44") (pintype "passive+no_connect"))
    )
    (net (code "56") (name "unconnected-(IC5-PDN-Pad30)") (class "Default")
      (node (ref "IC5") (pin "30") (pinfunction "PDN_30") (pintype "input+no_connect"))
    )
    (net (code "57") (name "unconnected-(IC10-NC-Pad17)") (class "Default")
      (node (ref "IC10") (pin "17") (pinfunction "NC_17") (pintype "passive+no_connect"))
    )
    (net (code "58") (name "unconnected-(IC10-NC-Pad44)") (class "Default")
      (node (ref "IC10") (pin "44") (pinfunction "NC_44") (pintype "passive+no_connect"))
    )
    (net (code "59") (name "unconnected-(IC10-PDN-Pad30)") (class "Default")
      (node (ref "IC10") (pin "30") (pinfunction "PDN_30") (pintype "input+no_connect"))
    )
  )
)
